# SCH_JK-BLDC-Encoder-Calibrator-Tester4_2.net
KiCad netlist of a schematic drawn in EasyEDA
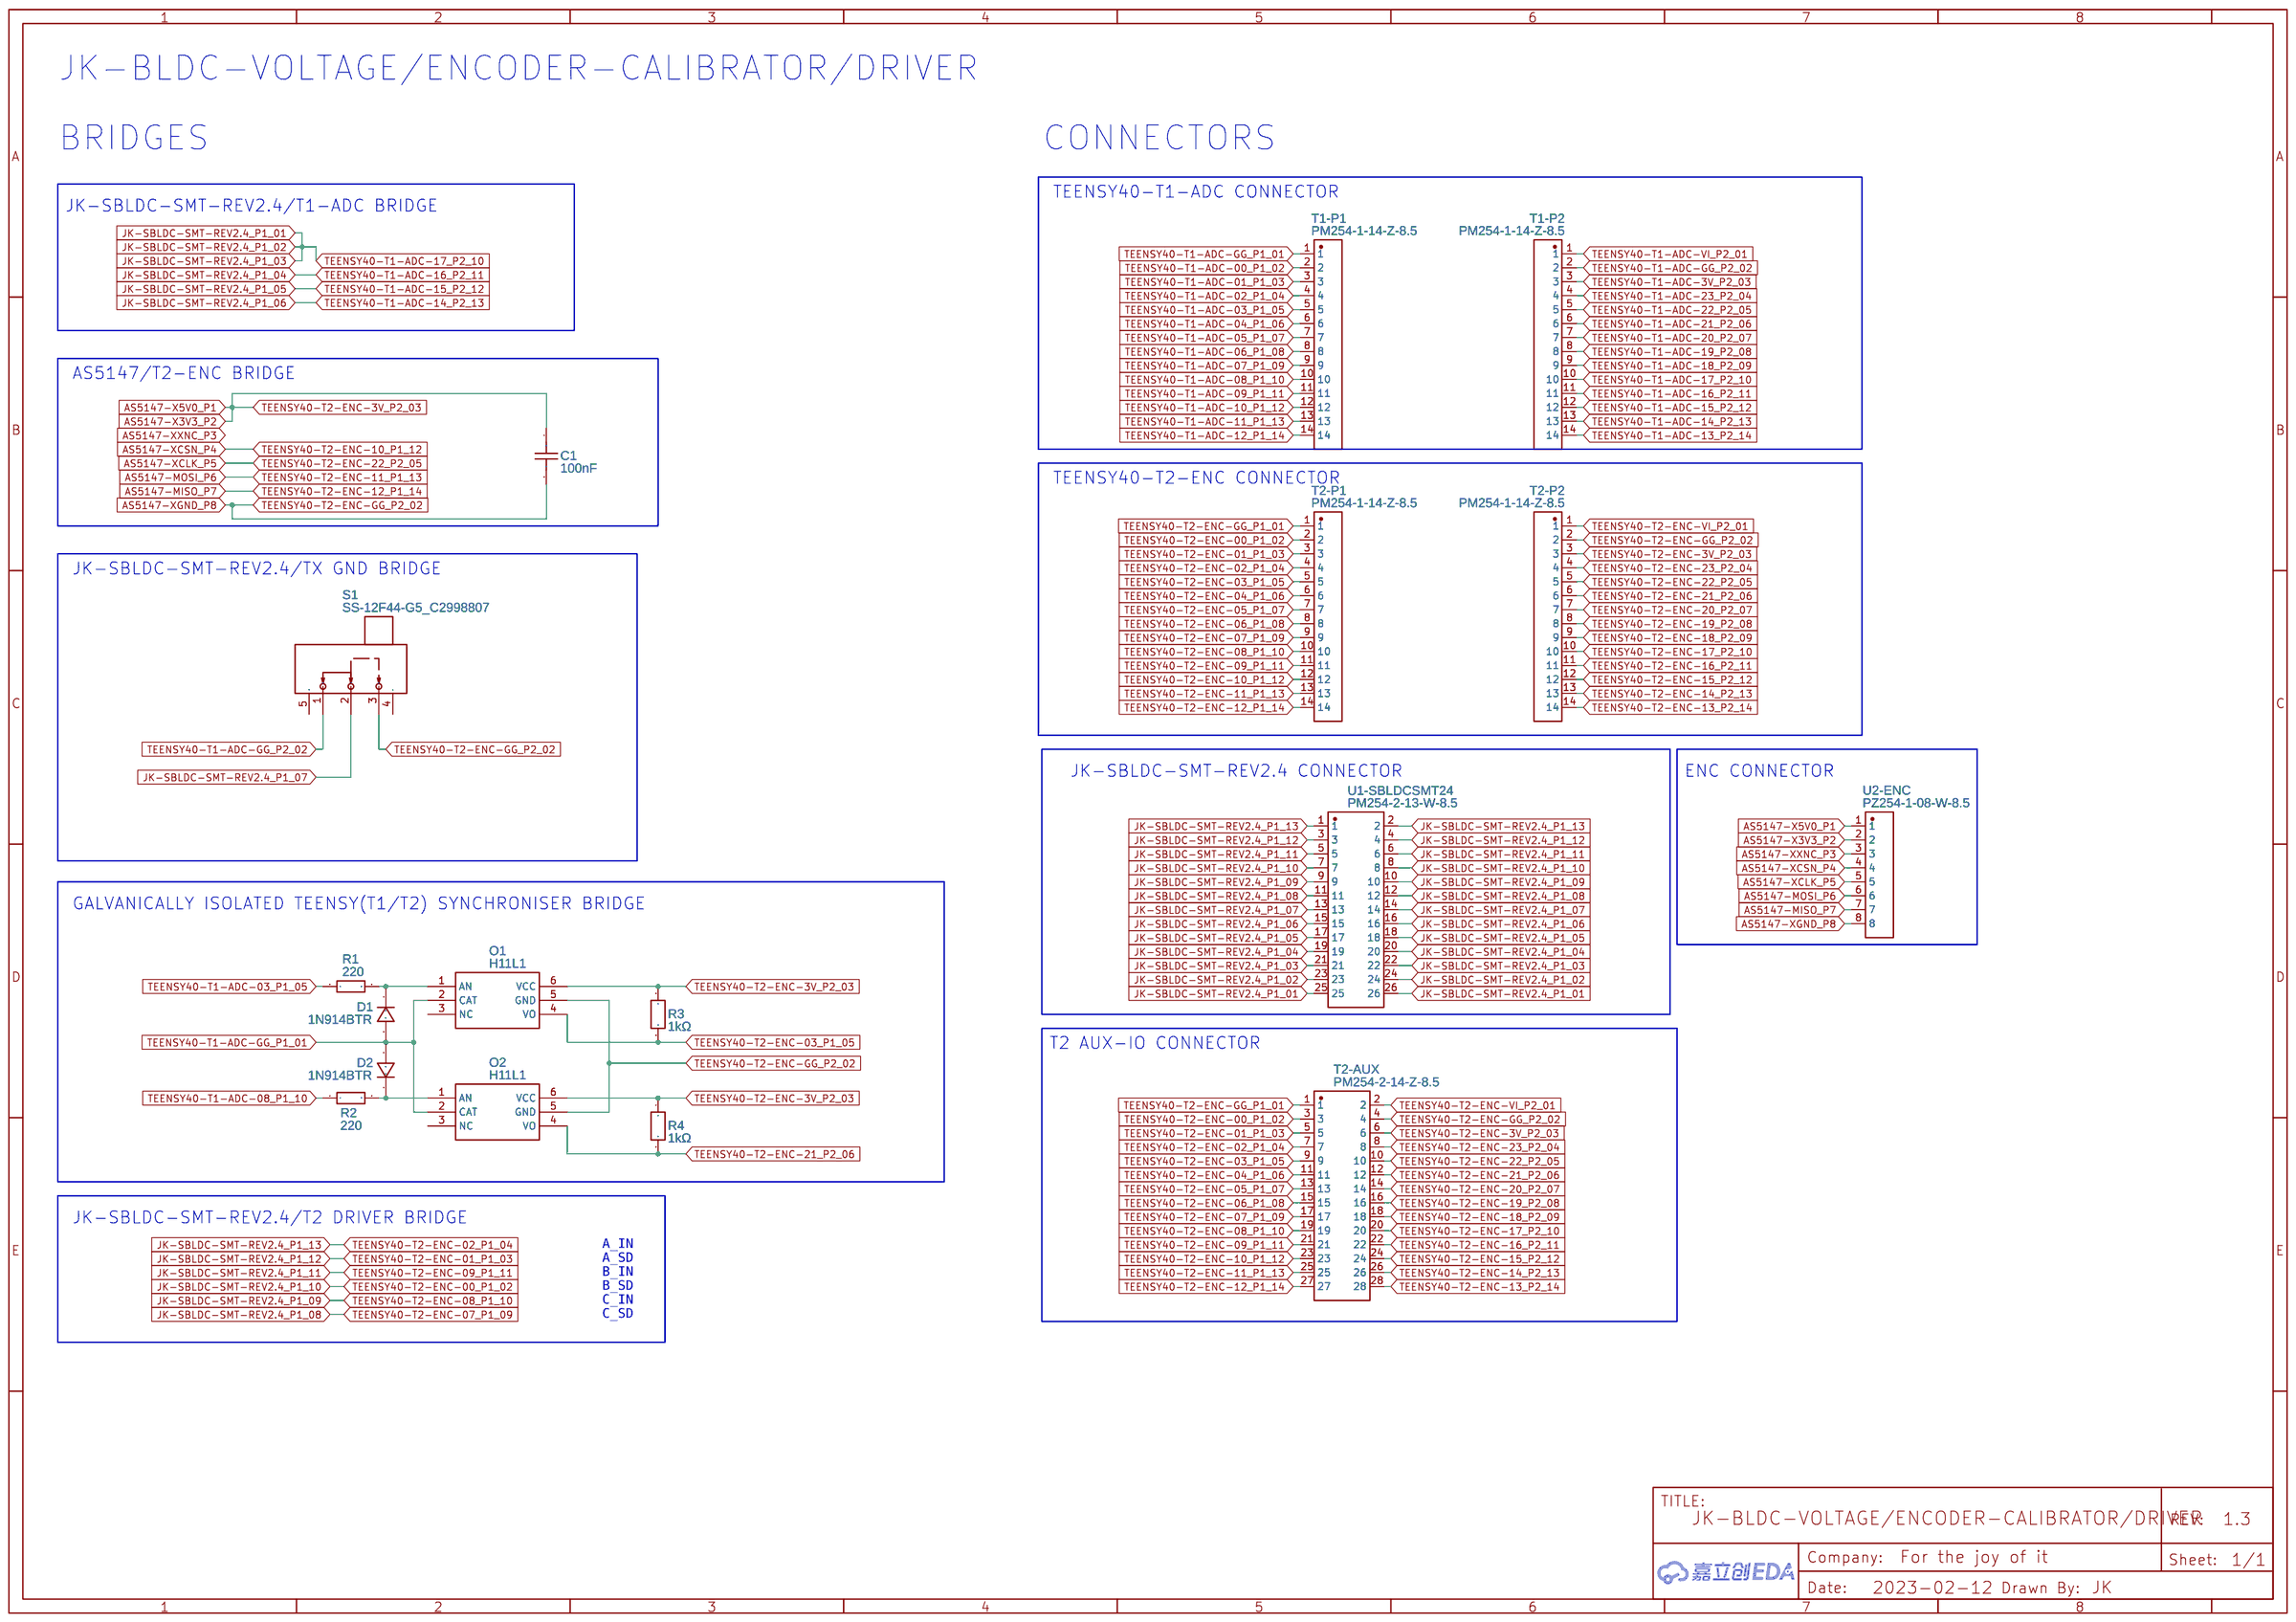
[diagram p0: schematic sheet]

(export (version "E")
  (design (tool "Eeschema 10.0.6"))
  (components
    (comp (ref "C1")
      (value "100nF")
      (fields
        (field (name "BOM_Manufacturer Part") "CC2A104ZC1ID3F7C30MF")
        (field (name "BOM_Supplier Part") "C254109")
      )
      (libsource (lib "") (part "CC2A104ZC1ID3F7C30MF"))
    )
    (comp (ref "D1")
      (value "1N914BTR")
      (fields (field (name "BOM_Supplier Part") "C258180"))
      (libsource (lib "") (part "1N914BTR"))
    )
    (comp (ref "D2")
      (value "1N914BTR")
      (fields (field (name "BOM_Supplier Part") "C258180"))
      (libsource (lib "") (part "1N914BTR_1"))
    )
    (comp (ref "O1")
      (value "H11L1")
      (fields (field (name "BOM_Supplier Part") "C78588"))
      (libsource (lib "") (part "H11L1"))
    )
    (comp (ref "O2")
      (value "H11L1")
      (fields (field (name "BOM_Supplier Part") "C78588"))
      (libsource (lib "") (part "H11L1"))
    )
    (comp (ref "R1")
      (value "220")
      (fields
        (field (name "BOM_Manufacturer Part") "MFR-25FTE52-220R")
        (field (name "BOM_Supplier Part") "C172985")
      )
      (libsource (lib "") (part "MFR-25FTE52-220R"))
    )
    (comp (ref "R2")
      (value "220")
      (fields
        (field (name "BOM_Manufacturer Part") "MFR-25FTE52-220R")
        (field (name "BOM_Supplier Part") "C172985")
      )
      (libsource (lib "") (part "MFR-25FTE52-220R"))
    )
    (comp (ref "R3")
      (value "1kΩ")
      (fields
        (field (name "BOM_Manufacturer Part") "MF1/4W-1KΩ±1%T52")
        (field (name "BOM_Supplier Part") "C713997")
      )
      (libsource (lib "") (part "MF1/4W-1KΩ±1%T52"))
    )
    (comp (ref "R4")
      (value "1kΩ")
      (fields
        (field (name "BOM_Manufacturer Part") "MF1/4W-1KΩ±1%T52")
        (field (name "BOM_Supplier Part") "C713997")
      )
      (libsource (lib "") (part "MF1/4W-1KΩ±1%T52"))
    )
    (comp (ref "S1")
      (value "SS-12F44-G5_C2998807")
      (fields
        (field (name "BOM_Manufacturer Part") "SS-12F44-G5")
        (field (name "BOM_Supplier Part") "C2998807")
      )
      (libsource (lib "") (part "SS-12F44-G5_C2998807"))
    )
    (comp (ref "T1-P1")
      (value "PM254-1-14-Z-8.5")
      (fields (field (name "BOM_Supplier Part") "C2897377"))
      (libsource (lib "") (part "PM254-1-14-Z-8.5_1"))
    )
    (comp (ref "T1-P2")
      (value "PM254-1-14-Z-8.5")
      (fields (field (name "BOM_Supplier Part") "C2897377"))
      (libsource (lib "") (part "PM254-1-14-Z-8.5_3"))
    )
    (comp (ref "T2-AUX")
      (value "PM254-2-14-Z-8.5")
      (fields (field (name "BOM_Supplier Part") "C2897415"))
      (libsource (lib "") (part "PM254-2-14-Z-8.5"))
    )
    (comp (ref "T2-P1")
      (value "PM254-1-14-Z-8.5")
      (fields (field (name "BOM_Supplier Part") "C2897377"))
      (libsource (lib "") (part "PM254-1-14-Z-8.5"))
    )
    (comp (ref "T2-P2")
      (value "PM254-1-14-Z-8.5")
      (fields (field (name "BOM_Supplier Part") "C2897377"))
      (libsource (lib "") (part "PM254-1-14-Z-8.5_2"))
    )
    (comp (ref "U1-SBLDCSMT24")
      (value "PM254-2-13-W-8.5")
      (fields (field (name "BOM_Supplier Part") "C2897433"))
      (libsource (lib "") (part "PM254-2-13-W-8.5"))
    )
    (comp (ref "U2-ENC")
      (value "PZ254-1-08-W-8.5")
      (fields (field (name "BOM_Supplier Part") "C2894950"))
      (libsource (lib "") (part "PZ254-1-08-W-8.5"))
    )
  )
  (nets
    (net (code "1") (name "AS5147-MISO_P7") (class "Default")
      (node (ref "T2-AUX") (pin "27") (pinfunction "27_27") (pintype "unspecified"))
      (node (ref "T2-P1") (pin "14") (pinfunction "14_14") (pintype "unspecified"))
      (node (ref "U2-ENC") (pin "7") (pinfunction "7_7") (pintype "unspecified"))
    )
    (net (code "2") (name "AS5147-MOSI_P6") (class "Default")
      (node (ref "T2-AUX") (pin "25") (pinfunction "25_25") (pintype "unspecified"))
      (node (ref "T2-P1") (pin "13") (pinfunction "13_13") (pintype "unspecified"))
      (node (ref "U2-ENC") (pin "6") (pinfunction "6_6") (pintype "unspecified"))
    )
    (net (code "3") (name "AS5147-X3V3_P2") (class "Default")
      (node (ref "C1") (pin "1") (pinfunction "1_1") (pintype "unspecified"))
      (node (ref "O1") (pin "6") (pinfunction "VCC_6") (pintype "unspecified"))
      (node (ref "O2") (pin "6") (pinfunction "VCC_6") (pintype "unspecified"))
      (node (ref "R3") (pin "1") (pinfunction "1_1") (pintype "unspecified"))
      (node (ref "R4") (pin "1") (pinfunction "1_1") (pintype "unspecified"))
      (node (ref "T2-AUX") (pin "6") (pinfunction "6_6") (pintype "unspecified"))
      (node (ref "T2-P2") (pin "3") (pinfunction "3_3") (pintype "unspecified"))
      (node (ref "U2-ENC") (pin "1") (pinfunction "1_1") (pintype "unspecified"))
      (node (ref "U2-ENC") (pin "2") (pinfunction "2_2") (pintype "unspecified"))
    )
    (net (code "4") (name "AS5147-XCLK_P5") (class "Default")
      (node (ref "T2-AUX") (pin "10") (pinfunction "10_10") (pintype "unspecified"))
      (node (ref "T2-P2") (pin "5") (pinfunction "5_5") (pintype "unspecified"))
      (node (ref "U2-ENC") (pin "5") (pinfunction "5_5") (pintype "unspecified"))
    )
    (net (code "5") (name "AS5147-XCSN_P4") (class "Default")
      (node (ref "T2-AUX") (pin "23") (pinfunction "23_23") (pintype "unspecified"))
      (node (ref "T2-P1") (pin "12") (pinfunction "12_12") (pintype "unspecified"))
      (node (ref "U2-ENC") (pin "4") (pinfunction "4_4") (pintype "unspecified"))
    )
    (net (code "6") (name "AS5147-XGND_P8") (class "Default")
      (node (ref "C1") (pin "2") (pinfunction "2_2") (pintype "unspecified"))
      (node (ref "O1") (pin "5") (pinfunction "GND_5") (pintype "unspecified"))
      (node (ref "O2") (pin "5") (pinfunction "GND_5") (pintype "unspecified"))
      (node (ref "S1") (pin "3") (pinfunction "3_3") (pintype "unspecified"))
      (node (ref "T2-AUX") (pin "4") (pinfunction "4_4") (pintype "unspecified"))
      (node (ref "T2-P2") (pin "2") (pinfunction "2_2") (pintype "unspecified"))
      (node (ref "U2-ENC") (pin "8") (pinfunction "8_8") (pintype "unspecified"))
    )
    (net (code "7") (name "AS5147-XXNC_P3") (class "Default")
      (node (ref "U2-ENC") (pin "3") (pinfunction "3_3") (pintype "unspecified"))
    )
    (net (code "8") (name "JK-SBLDC-SMT-REV2.4_P1_01") (class "Default")
      (node (ref "T1-P2") (pin "10") (pinfunction "10_10") (pintype "unspecified"))
      (node (ref "U1-SBLDCSMT24") (pin "21") (pinfunction "21_21") (pintype "unspecified"))
      (node (ref "U1-SBLDCSMT24") (pin "22") (pinfunction "22_22") (pintype "unspecified"))
      (node (ref "U1-SBLDCSMT24") (pin "23") (pinfunction "23_23") (pintype "unspecified"))
      (node (ref "U1-SBLDCSMT24") (pin "24") (pinfunction "24_24") (pintype "unspecified"))
      (node (ref "U1-SBLDCSMT24") (pin "25") (pinfunction "25_25") (pintype "unspecified"))
      (node (ref "U1-SBLDCSMT24") (pin "26") (pinfunction "26_26") (pintype "unspecified"))
    )
    (net (code "9") (name "JK-SBLDC-SMT-REV2.4_P1_04") (class "Default")
      (node (ref "T1-P2") (pin "11") (pinfunction "11_11") (pintype "unspecified"))
      (node (ref "U1-SBLDCSMT24") (pin "19") (pinfunction "19_19") (pintype "unspecified"))
      (node (ref "U1-SBLDCSMT24") (pin "20") (pinfunction "20_20") (pintype "unspecified"))
    )
    (net (code "10") (name "JK-SBLDC-SMT-REV2.4_P1_05") (class "Default")
      (node (ref "T1-P2") (pin "12") (pinfunction "12_12") (pintype "unspecified"))
      (node (ref "U1-SBLDCSMT24") (pin "17") (pinfunction "17_17") (pintype "unspecified"))
      (node (ref "U1-SBLDCSMT24") (pin "18") (pinfunction "18_18") (pintype "unspecified"))
    )
    (net (code "11") (name "JK-SBLDC-SMT-REV2.4_P1_06") (class "Default")
      (node (ref "T1-P2") (pin "13") (pinfunction "13_13") (pintype "unspecified"))
      (node (ref "U1-SBLDCSMT24") (pin "15") (pinfunction "15_15") (pintype "unspecified"))
      (node (ref "U1-SBLDCSMT24") (pin "16") (pinfunction "16_16") (pintype "unspecified"))
    )
    (net (code "12") (name "JK-SBLDC-SMT-REV2.4_P1_07") (class "Default")
      (node (ref "S1") (pin "2") (pinfunction "2_2") (pintype "unspecified"))
      (node (ref "U1-SBLDCSMT24") (pin "13") (pinfunction "13_13") (pintype "unspecified"))
      (node (ref "U1-SBLDCSMT24") (pin "14") (pinfunction "14_14") (pintype "unspecified"))
    )
    (net (code "13") (name "JK-SBLDC-SMT-REV2.4_P1_08") (class "Default")
      (node (ref "T2-AUX") (pin "17") (pinfunction "17_17") (pintype "unspecified"))
      (node (ref "T2-P1") (pin "9") (pinfunction "9_9") (pintype "unspecified"))
      (node (ref "U1-SBLDCSMT24") (pin "11") (pinfunction "11_11") (pintype "unspecified"))
      (node (ref "U1-SBLDCSMT24") (pin "12") (pinfunction "12_12") (pintype "unspecified"))
    )
    (net (code "14") (name "JK-SBLDC-SMT-REV2.4_P1_09") (class "Default")
      (node (ref "T2-AUX") (pin "19") (pinfunction "19_19") (pintype "unspecified"))
      (node (ref "T2-P1") (pin "10") (pinfunction "10_10") (pintype "unspecified"))
      (node (ref "U1-SBLDCSMT24") (pin "10") (pinfunction "10_10") (pintype "unspecified"))
      (node (ref "U1-SBLDCSMT24") (pin "9") (pinfunction "9_9") (pintype "unspecified"))
    )
    (net (code "15") (name "JK-SBLDC-SMT-REV2.4_P1_10") (class "Default")
      (node (ref "T2-AUX") (pin "3") (pinfunction "3_3") (pintype "unspecified"))
      (node (ref "T2-P1") (pin "2") (pinfunction "2_2") (pintype "unspecified"))
      (node (ref "U1-SBLDCSMT24") (pin "7") (pinfunction "7_7") (pintype "unspecified"))
      (node (ref "U1-SBLDCSMT24") (pin "8") (pinfunction "8_8") (pintype "unspecified"))
    )
    (net (code "16") (name "JK-SBLDC-SMT-REV2.4_P1_11") (class "Default")
      (node (ref "T2-AUX") (pin "21") (pinfunction "21_21") (pintype "unspecified"))
      (node (ref "T2-P1") (pin "11") (pinfunction "11_11") (pintype "unspecified"))
      (node (ref "U1-SBLDCSMT24") (pin "5") (pinfunction "5_5") (pintype "unspecified"))
      (node (ref "U1-SBLDCSMT24") (pin "6") (pinfunction "6_6") (pintype "unspecified"))
    )
    (net (code "17") (name "JK-SBLDC-SMT-REV2.4_P1_12") (class "Default")
      (node (ref "T2-AUX") (pin "5") (pinfunction "5_5") (pintype "unspecified"))
      (node (ref "T2-P1") (pin "3") (pinfunction "3_3") (pintype "unspecified"))
      (node (ref "U1-SBLDCSMT24") (pin "3") (pinfunction "3_3") (pintype "unspecified"))
      (node (ref "U1-SBLDCSMT24") (pin "4") (pinfunction "4_4") (pintype "unspecified"))
    )
    (net (code "18") (name "JK-SBLDC-SMT-REV2.4_P1_13") (class "Default")
      (node (ref "T2-AUX") (pin "7") (pinfunction "7_7") (pintype "unspecified"))
      (node (ref "T2-P1") (pin "4") (pinfunction "4_4") (pintype "unspecified"))
      (node (ref "U1-SBLDCSMT24") (pin "1") (pinfunction "1_1") (pintype "unspecified"))
      (node (ref "U1-SBLDCSMT24") (pin "2") (pinfunction "2_2") (pintype "unspecified"))
    )
    (net (code "19") (name "Net-(O1-AN)") (class "Default")
      (node (ref "D1") (pin "1") (pinfunction "1_1") (pintype "unspecified"))
      (node (ref "O1") (pin "1") (pinfunction "AN_1") (pintype "unspecified"))
      (node (ref "R1") (pin "2") (pinfunction "2_2") (pintype "unspecified"))
    )
    (net (code "20") (name "Net-(O2-AN)") (class "Default")
      (node (ref "D2") (pin "1") (pinfunction "1_1") (pintype "unspecified"))
      (node (ref "O2") (pin "1") (pinfunction "AN_1") (pintype "unspecified"))
      (node (ref "R2") (pin "2") (pinfunction "2_2") (pintype "unspecified"))
    )
    (net (code "21") (name "TEENSY40-T1-ADC-00_P1_02") (class "Default")
      (node (ref "T1-P1") (pin "2") (pinfunction "2_2") (pintype "unspecified"))
    )
    (net (code "22") (name "TEENSY40-T1-ADC-01_P1_03") (class "Default")
      (node (ref "T1-P1") (pin "3") (pinfunction "3_3") (pintype "unspecified"))
    )
    (net (code "23") (name "TEENSY40-T1-ADC-02_P1_04") (class "Default")
      (node (ref "T1-P1") (pin "4") (pinfunction "4_4") (pintype "unspecified"))
    )
    (net (code "24") (name "TEENSY40-T1-ADC-3V_P2_03") (class "Default")
      (node (ref "T1-P2") (pin "3") (pinfunction "3_3") (pintype "unspecified"))
    )
    (net (code "25") (name "TEENSY40-T1-ADC-03_P1_05") (class "Default")
      (node (ref "R1") (pin "1") (pinfunction "1_1") (pintype "unspecified"))
      (node (ref "T1-P1") (pin "5") (pinfunction "5_5") (pintype "unspecified"))
    )
    (net (code "26") (name "TEENSY40-T1-ADC-04_P1_06") (class "Default")
      (node (ref "T1-P1") (pin "6") (pinfunction "6_6") (pintype "unspecified"))
    )
    (net (code "27") (name "TEENSY40-T1-ADC-05_P1_07") (class "Default")
      (node (ref "T1-P1") (pin "7") (pinfunction "7_7") (pintype "unspecified"))
    )
    (net (code "28") (name "TEENSY40-T1-ADC-06_P1_08") (class "Default")
      (node (ref "T1-P1") (pin "8") (pinfunction "8_8") (pintype "unspecified"))
    )
    (net (code "29") (name "TEENSY40-T1-ADC-07_P1_09") (class "Default")
      (node (ref "T1-P1") (pin "9") (pinfunction "9_9") (pintype "unspecified"))
    )
    (net (code "30") (name "TEENSY40-T1-ADC-08_P1_10") (class "Default")
      (node (ref "R2") (pin "1") (pinfunction "1_1") (pintype "unspecified"))
      (node (ref "T1-P1") (pin "10") (pinfunction "10_10") (pintype "unspecified"))
    )
    (net (code "31") (name "TEENSY40-T1-ADC-09_P1_11") (class "Default")
      (node (ref "T1-P1") (pin "11") (pinfunction "11_11") (pintype "unspecified"))
    )
    (net (code "32") (name "TEENSY40-T1-ADC-10_P1_12") (class "Default")
      (node (ref "T1-P1") (pin "12") (pinfunction "12_12") (pintype "unspecified"))
    )
    (net (code "33") (name "TEENSY40-T1-ADC-11_P1_13") (class "Default")
      (node (ref "T1-P1") (pin "13") (pinfunction "13_13") (pintype "unspecified"))
    )
    (net (code "34") (name "TEENSY40-T1-ADC-12_P1_14") (class "Default")
      (node (ref "T1-P1") (pin "14") (pinfunction "14_14") (pintype "unspecified"))
    )
    (net (code "35") (name "TEENSY40-T1-ADC-13_P2_14") (class "Default")
      (node (ref "T1-P2") (pin "14") (pinfunction "14_14") (pintype "unspecified"))
    )
    (net (code "36") (name "TEENSY40-T1-ADC-18_P2_09") (class "Default")
      (node (ref "T1-P2") (pin "9") (pinfunction "9_9") (pintype "unspecified"))
    )
    (net (code "37") (name "TEENSY40-T1-ADC-19_P2_08") (class "Default")
      (node (ref "T1-P2") (pin "8") (pinfunction "8_8") (pintype "unspecified"))
    )
    (net (code "38") (name "TEENSY40-T1-ADC-20_P2_07") (class "Default")
      (node (ref "T1-P2") (pin "7") (pinfunction "7_7") (pintype "unspecified"))
    )
    (net (code "39") (name "TEENSY40-T1-ADC-21_P2_06") (class "Default")
      (node (ref "T1-P2") (pin "6") (pinfunction "6_6") (pintype "unspecified"))
    )
    (net (code "40") (name "TEENSY40-T1-ADC-22_P2_05") (class "Default")
      (node (ref "T1-P2") (pin "5") (pinfunction "5_5") (pintype "unspecified"))
    )
    (net (code "41") (name "TEENSY40-T1-ADC-23_P2_04") (class "Default")
      (node (ref "T1-P2") (pin "4") (pinfunction "4_4") (pintype "unspecified"))
    )
    (net (code "42") (name "TEENSY40-T1-ADC-GG_P1_01") (class "Default")
      (node (ref "D1") (pin "2") (pinfunction "2_2") (pintype "unspecified"))
      (node (ref "D2") (pin "2") (pinfunction "2_2") (pintype "unspecified"))
      (node (ref "O1") (pin "2") (pinfunction "CAT_2") (pintype "unspecified"))
      (node (ref "O2") (pin "2") (pinfunction "CAT_2") (pintype "unspecified"))
      (node (ref "T1-P1") (pin "1") (pinfunction "1_1") (pintype "unspecified"))
    )
    (net (code "43") (name "TEENSY40-T1-ADC-GG_P2_02") (class "Default")
      (node (ref "S1") (pin "1") (pinfunction "1_1") (pintype "unspecified"))
      (node (ref "T1-P2") (pin "2") (pinfunction "2_2") (pintype "unspecified"))
    )
    (net (code "44") (name "TEENSY40-T1-ADC-VI_P2_01") (class "Default")
      (node (ref "T1-P2") (pin "1") (pinfunction "1_1") (pintype "unspecified"))
    )
    (net (code "45") (name "TEENSY40-T2-ENC-03_P1_05") (class "Default")
      (node (ref "O1") (pin "4") (pinfunction "VO_4") (pintype "unspecified"))
      (node (ref "R3") (pin "2") (pinfunction "2_2") (pintype "unspecified"))
      (node (ref "T2-AUX") (pin "9") (pinfunction "9_9") (pintype "unspecified"))
      (node (ref "T2-P1") (pin "5") (pinfunction "5_5") (pintype "unspecified"))
    )
    (net (code "46") (name "TEENSY40-T2-ENC-04_P1_06") (class "Default")
      (node (ref "T2-AUX") (pin "11") (pinfunction "11_11") (pintype "unspecified"))
      (node (ref "T2-P1") (pin "6") (pinfunction "6_6") (pintype "unspecified"))
    )
    (net (code "47") (name "TEENSY40-T2-ENC-05_P1_07") (class "Default")
      (node (ref "T2-AUX") (pin "13") (pinfunction "13_13") (pintype "unspecified"))
      (node (ref "T2-P1") (pin "7") (pinfunction "7_7") (pintype "unspecified"))
    )
    (net (code "48") (name "TEENSY40-T2-ENC-06_P1_08") (class "Default")
      (node (ref "T2-AUX") (pin "15") (pinfunction "15_15") (pintype "unspecified"))
      (node (ref "T2-P1") (pin "8") (pinfunction "8_8") (pintype "unspecified"))
    )
    (net (code "49") (name "TEENSY40-T2-ENC-13_P2_14") (class "Default")
      (node (ref "T2-AUX") (pin "28") (pinfunction "28_28") (pintype "unspecified"))
      (node (ref "T2-P2") (pin "14") (pinfunction "14_14") (pintype "unspecified"))
    )
    (net (code "50") (name "TEENSY40-T2-ENC-14_P2_13") (class "Default")
      (node (ref "T2-AUX") (pin "26") (pinfunction "26_26") (pintype "unspecified"))
      (node (ref "T2-P2") (pin "13") (pinfunction "13_13") (pintype "unspecified"))
    )
    (net (code "51") (name "TEENSY40-T2-ENC-15_P2_12") (class "Default")
      (node (ref "T2-AUX") (pin "24") (pinfunction "24_24") (pintype "unspecified"))
      (node (ref "T2-P2") (pin "12") (pinfunction "12_12") (pintype "unspecified"))
    )
    (net (code "52") (name "TEENSY40-T2-ENC-16_P2_11") (class "Default")
      (node (ref "T2-AUX") (pin "22") (pinfunction "22_22") (pintype "unspecified"))
      (node (ref "T2-P2") (pin "11") (pinfunction "11_11") (pintype "unspecified"))
    )
    (net (code "53") (name "TEENSY40-T2-ENC-17_P2_10") (class "Default")
      (node (ref "T2-AUX") (pin "20") (pinfunction "20_20") (pintype "unspecified"))
      (node (ref "T2-P2") (pin "10") (pinfunction "10_10") (pintype "unspecified"))
    )
    (net (code "54") (name "TEENSY40-T2-ENC-18_P2_09") (class "Default")
      (node (ref "T2-AUX") (pin "18") (pinfunction "18_18") (pintype "unspecified"))
      (node (ref "T2-P2") (pin "9") (pinfunction "9_9") (pintype "unspecified"))
    )
    (net (code "55") (name "TEENSY40-T2-ENC-19_P2_08") (class "Default")
      (node (ref "T2-AUX") (pin "16") (pinfunction "16_16") (pintype "unspecified"))
      (node (ref "T2-P2") (pin "8") (pinfunction "8_8") (pintype "unspecified"))
    )
    (net (code "56") (name "TEENSY40-T2-ENC-20_P2_07") (class "Default")
      (node (ref "T2-AUX") (pin "14") (pinfunction "14_14") (pintype "unspecified"))
      (node (ref "T2-P2") (pin "7") (pinfunction "7_7") (pintype "unspecified"))
    )
    (net (code "57") (name "TEENSY40-T2-ENC-21_P2_06") (class "Default")
      (node (ref "O2") (pin "4") (pinfunction "VO_4") (pintype "unspecified"))
      (node (ref "R4") (pin "2") (pinfunction "2_2") (pintype "unspecified"))
      (node (ref "T2-AUX") (pin "12") (pinfunction "12_12") (pintype "unspecified"))
      (node (ref "T2-P2") (pin "6") (pinfunction "6_6") (pintype "unspecified"))
    )
    (net (code "58") (name "TEENSY40-T2-ENC-23_P2_04") (class "Default")
      (node (ref "T2-AUX") (pin "8") (pinfunction "8_8") (pintype "unspecified"))
      (node (ref "T2-P2") (pin "4") (pinfunction "4_4") (pintype "unspecified"))
    )
    (net (code "59") (name "TEENSY40-T2-ENC-GG_P1_01") (class "Default")
      (node (ref "T2-AUX") (pin "1") (pinfunction "1_1") (pintype "unspecified"))
      (node (ref "T2-P1") (pin "1") (pinfunction "1_1") (pintype "unspecified"))
    )
    (net (code "60") (name "TEENSY40-T2-ENC-VI_P2_01") (class "Default")
      (node (ref "T2-AUX") (pin "2") (pinfunction "2_2") (pintype "unspecified"))
      (node (ref "T2-P2") (pin "1") (pinfunction "1_1") (pintype "unspecified"))
    )
    (net (code "61") (name "unconnected-(O1-NC-Pad3)") (class "Default")
      (node (ref "O1") (pin "3") (pinfunction "NC_3") (pintype "unspecified"))
    )
    (net (code "62") (name "unconnected-(O2-NC-Pad3)") (class "Default")
      (node (ref "O2") (pin "3") (pinfunction "NC_3") (pintype "unspecified"))
    )
    (net (code "63") (name "unconnected-(S1-Pad4)") (class "Default")
      (node (ref "S1") (pin "4") (pinfunction "4_4") (pintype "unspecified"))
    )
    (net (code "64") (name "unconnected-(S1-Pad5)") (class "Default")
      (node (ref "S1") (pin "5") (pinfunction "5_5") (pintype "unspecified"))
    )
  )
)
